# Sensor_SINCOS.net
KiCad netlist of a schematic drawn in Altium Designer
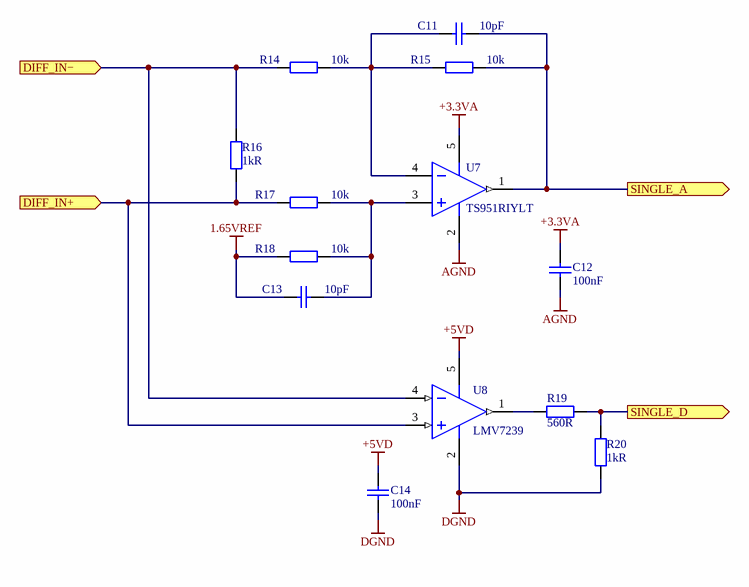
[diagram p0: Sensor_SINCOS.SchDoc]

(export (version "E")
  (design (tool "Eeschema 10.0.6"))
  (components
    (comp (ref "C11")
      (value "10pF")
      (footprint "InterfaceBoard:CAPC1608X08N")
      (description "10pF ±10% 10V Condensateurs céramique X7R 0603 (1608 métrique)")
      (fields (field (name "Comment") "CAP CER 10pF 0603"))
      (libsource (lib "InterfaceBoard") (part "CAP CER 10pF 10% 10V 0603"))
    )
    (comp (ref "C12")
      (value "100nF")
      (footprint "InterfaceBoard:CAPC1608X08N")
      (description "100nF ±10% 10V Condensateurs céramique X7R 0603 (1608 métrique)")
      (fields (field (name "Comment") "CAP CER 100nF 0603"))
      (libsource (lib "InterfaceBoard") (part "CAP CER 100nF 10% 10V 0603"))
    )
    (comp (ref "C13")
      (value "10pF")
      (footprint "InterfaceBoard:CAPC1608X08N")
      (description "10pF ±10% 10V Condensateurs céramique X7R 0603 (1608 métrique)")
      (fields (field (name "Comment") "CAP CER 10pF 0603"))
      (libsource (lib "InterfaceBoard") (part "CAP CER 10pF 10% 10V 0603"))
    )
    (comp (ref "C14")
      (value "100nF")
      (footprint "InterfaceBoard:CAPC1608X08N")
      (description "100nF ±10% 10V Condensateurs céramique X7R 0603 (1608 métrique)")
      (fields (field (name "Comment") "CAP CER 100nF 0603"))
      (libsource (lib "InterfaceBoard") (part "CAP CER 100nF 10% 10V 0603"))
    )
    (comp (ref "R14")
      (value "10k")
      (footprint "InterfaceBoard:RESC1508X04N")
      (description "10 kOhms ±1% 0,1W, 1/10W Pavé résistif 0603 (1608 métrique) AutomobileAEC-Q200 Couche épaisse")
      (fields (field (name "Comment") "RES SMD 10K 0603"))
      (libsource (lib "InterfaceBoard") (part "RES SMD 10K OHM 1% 1/10W 0603"))
    )
    (comp (ref "R15")
      (value "10k")
      (footprint "InterfaceBoard:RESC1508X04N")
      (description "10 kOhms ±1% 0,1W, 1/10W Pavé résistif 0603 (1608 métrique) AutomobileAEC-Q200 Couche épaisse")
      (fields (field (name "Comment") "RES SMD 10K 0603"))
      (libsource (lib "InterfaceBoard") (part "RES SMD 10K OHM 1% 1/10W 0603"))
    )
    (comp (ref "R16")
      (value "1kR")
      (footprint "InterfaceBoard:RESC1508X04N")
      (description "1 kOhms ±1% 0,1W, 1/10W Pavé résistif 0603 (1608 métrique) AutomobileAEC-Q200 Couche épaisse")
      (fields (field (name "Comment") "RES SMD 1K 0603"))
      (libsource (lib "InterfaceBoard") (part "RES SMD 1K OHM 1% 1/10W 0603"))
    )
    (comp (ref "R17")
      (value "10k")
      (footprint "InterfaceBoard:RESC1508X04N")
      (description "10 kOhms ±1% 0,1W, 1/10W Pavé résistif 0603 (1608 métrique) AutomobileAEC-Q200 Couche épaisse")
      (fields (field (name "Comment") "RES SMD 10K 0603"))
      (libsource (lib "InterfaceBoard") (part "RES SMD 10K OHM 1% 1/10W 0603"))
    )
    (comp (ref "R18")
      (value "10k")
      (footprint "InterfaceBoard:RESC1508X04N")
      (description "10 kOhms ±1% 0,1W, 1/10W Pavé résistif 0603 (1608 métrique) AutomobileAEC-Q200 Couche épaisse")
      (fields (field (name "Comment") "RES SMD 10K 0603"))
      (libsource (lib "") (part "RES SMD 10K OHM 1% 1/10W 0603_1"))
    )
    (comp (ref "R19")
      (value "560R")
      (footprint "InterfaceBoard:RESC1508X04N")
      (description "560 Ohms ±1% 0,1W, 1/10W Pavé résistif 0603 (1608 métrique) AutomobileAEC-Q200 Couche épaisse")
      (fields (field (name "Comment") "RES SMD 560R 0603"))
      (libsource (lib "InterfaceBoard") (part "RES SMD 560 OHM 0.1% 1/10W 0603"))
    )
    (comp (ref "R20")
      (value "1kR")
      (footprint "InterfaceBoard:RESC1508X04N")
      (description "1 kOhms ±1% 0,1W, 1/10W Pavé résistif 0603 (1608 métrique) AutomobileAEC-Q200 Couche épaisse")
      (fields (field (name "Comment") "RES SMD 1K 0603"))
      (libsource (lib "InterfaceBoard") (part "RES SMD 1K OHM 1% 1/10W 0603"))
    )
    (comp (ref "U7")
      (value "TS951RIYLT")
      (footprint "InterfaceBoard:SOT95P280X145-5N")
      (description "CMOS Amplificateurs 1 Circuits Pôle à pôle SOT-23-5")
      (fields (field (name "Comment") "OPAMP 1 CIRCUIT"))
      (libsource (lib "InterfaceBoard") (part "IC OPAMP GP 1 CIRCUIT SOT23-5"))
    )
    (comp (ref "U8")
      (value "LMV7239")
      (footprint "InterfaceBoard:SOT95P280X145-5N")
      (description "Comparateurs Usage général Pousser-tirer, rail-à-rail SOT-23-5")
      (fields (field (name "Comment") "COMP 1 CIRCUIT"))
      (libsource (lib "InterfaceBoard") (part "IC COMP PUSH-PULL 1 CIRCUIT SOT-23-5"))
    )
  )
  (nets
    (net (code "1") (name "+3.3VA") (class "Default")
      (node (ref "C12") (pin "2") (pinfunction "2_2") (pintype "passive"))
      (node (ref "U7") (pin "5") (pinfunction "IN-_5") (pintype "power_in"))
    )
    (net (code "2") (name "+5VD") (class "Default")
      (node (ref "C14") (pin "2") (pinfunction "2_2") (pintype "passive"))
      (node (ref "U8") (pin "5") (pinfunction "IN-_5") (pintype "power_in"))
    )
    (net (code "3") (name "/DIFF_IN+") (class "Default")
      (node (ref "R16") (pin "1") (pinfunction "1_1") (pintype "passive"))
      (node (ref "R17") (pin "1") (pinfunction "1_1") (pintype "passive"))
      (node (ref "U8") (pin "3") (pinfunction "IN+_3") (pintype "input"))
    )
    (net (code "4") (name "/DIFF_IN−") (class "Default")
      (node (ref "R14") (pin "1") (pinfunction "1_1") (pintype "passive"))
      (node (ref "R16") (pin "2") (pinfunction "2_2") (pintype "passive"))
      (node (ref "U8") (pin "4") (pinfunction "IN-_4") (pintype "input"))
    )
    (net (code "5") (name "/SINGLE_A") (class "Default")
      (node (ref "C11") (pin "2") (pinfunction "2_2") (pintype "passive"))
      (node (ref "R15") (pin "2") (pinfunction "2_2") (pintype "passive"))
      (node (ref "U7") (pin "1") (pinfunction "OUT_1") (pintype "output"))
    )
    (net (code "6") (name "/SINGLE_D") (class "Default")
      (node (ref "R19") (pin "1") (pinfunction "1_1") (pintype "passive"))
      (node (ref "R20") (pin "2") (pinfunction "2_2") (pintype "passive"))
    )
    (net (code "7") (name "1.65VREF") (class "Default")
      (node (ref "C13") (pin "2") (pinfunction "2_2") (pintype "passive"))
      (node (ref "R18") (pin "2") (pinfunction "2_2") (pintype "passive"))
    )
    (net (code "8") (name "AGND") (class "Default")
      (node (ref "C12") (pin "1") (pinfunction "1_1") (pintype "passive"))
      (node (ref "U7") (pin "2") (pinfunction "IN-_2") (pintype "power_in"))
    )
    (net (code "9") (name "DGND") (class "Default")
      (node (ref "C14") (pin "1") (pinfunction "1_1") (pintype "passive"))
      (node (ref "R20") (pin "1") (pinfunction "1_1") (pintype "passive"))
      (node (ref "U8") (pin "2") (pinfunction "IN-_2") (pintype "power_in"))
    )
    (net (code "10") (name "Net-(C11-Pad1)") (class "Default")
      (node (ref "C11") (pin "1") (pinfunction "1_1") (pintype "passive"))
      (node (ref "R14") (pin "2") (pinfunction "2_2") (pintype "passive"))
      (node (ref "R15") (pin "1") (pinfunction "1_1") (pintype "passive"))
      (node (ref "U7") (pin "4") (pinfunction "IN-_4") (pintype "passive"))
    )
    (net (code "11") (name "Net-(U7-IN+)") (class "Default")
      (node (ref "C13") (pin "1") (pinfunction "1_1") (pintype "passive"))
      (node (ref "R17") (pin "2") (pinfunction "2_2") (pintype "passive"))
      (node (ref "R18") (pin "1") (pinfunction "1_1") (pintype "passive"))
      (node (ref "U7") (pin "3") (pinfunction "IN+_3") (pintype "passive"))
    )
    (net (code "12") (name "Net-(U8-OUT)") (class "Default")
      (node (ref "R19") (pin "2") (pinfunction "2_2") (pintype "passive"))
      (node (ref "U8") (pin "1") (pinfunction "OUT_1") (pintype "output"))
    )
  )
)
